# wavefreak.net
KiCad netlist of a schematic drawn in EAGLE
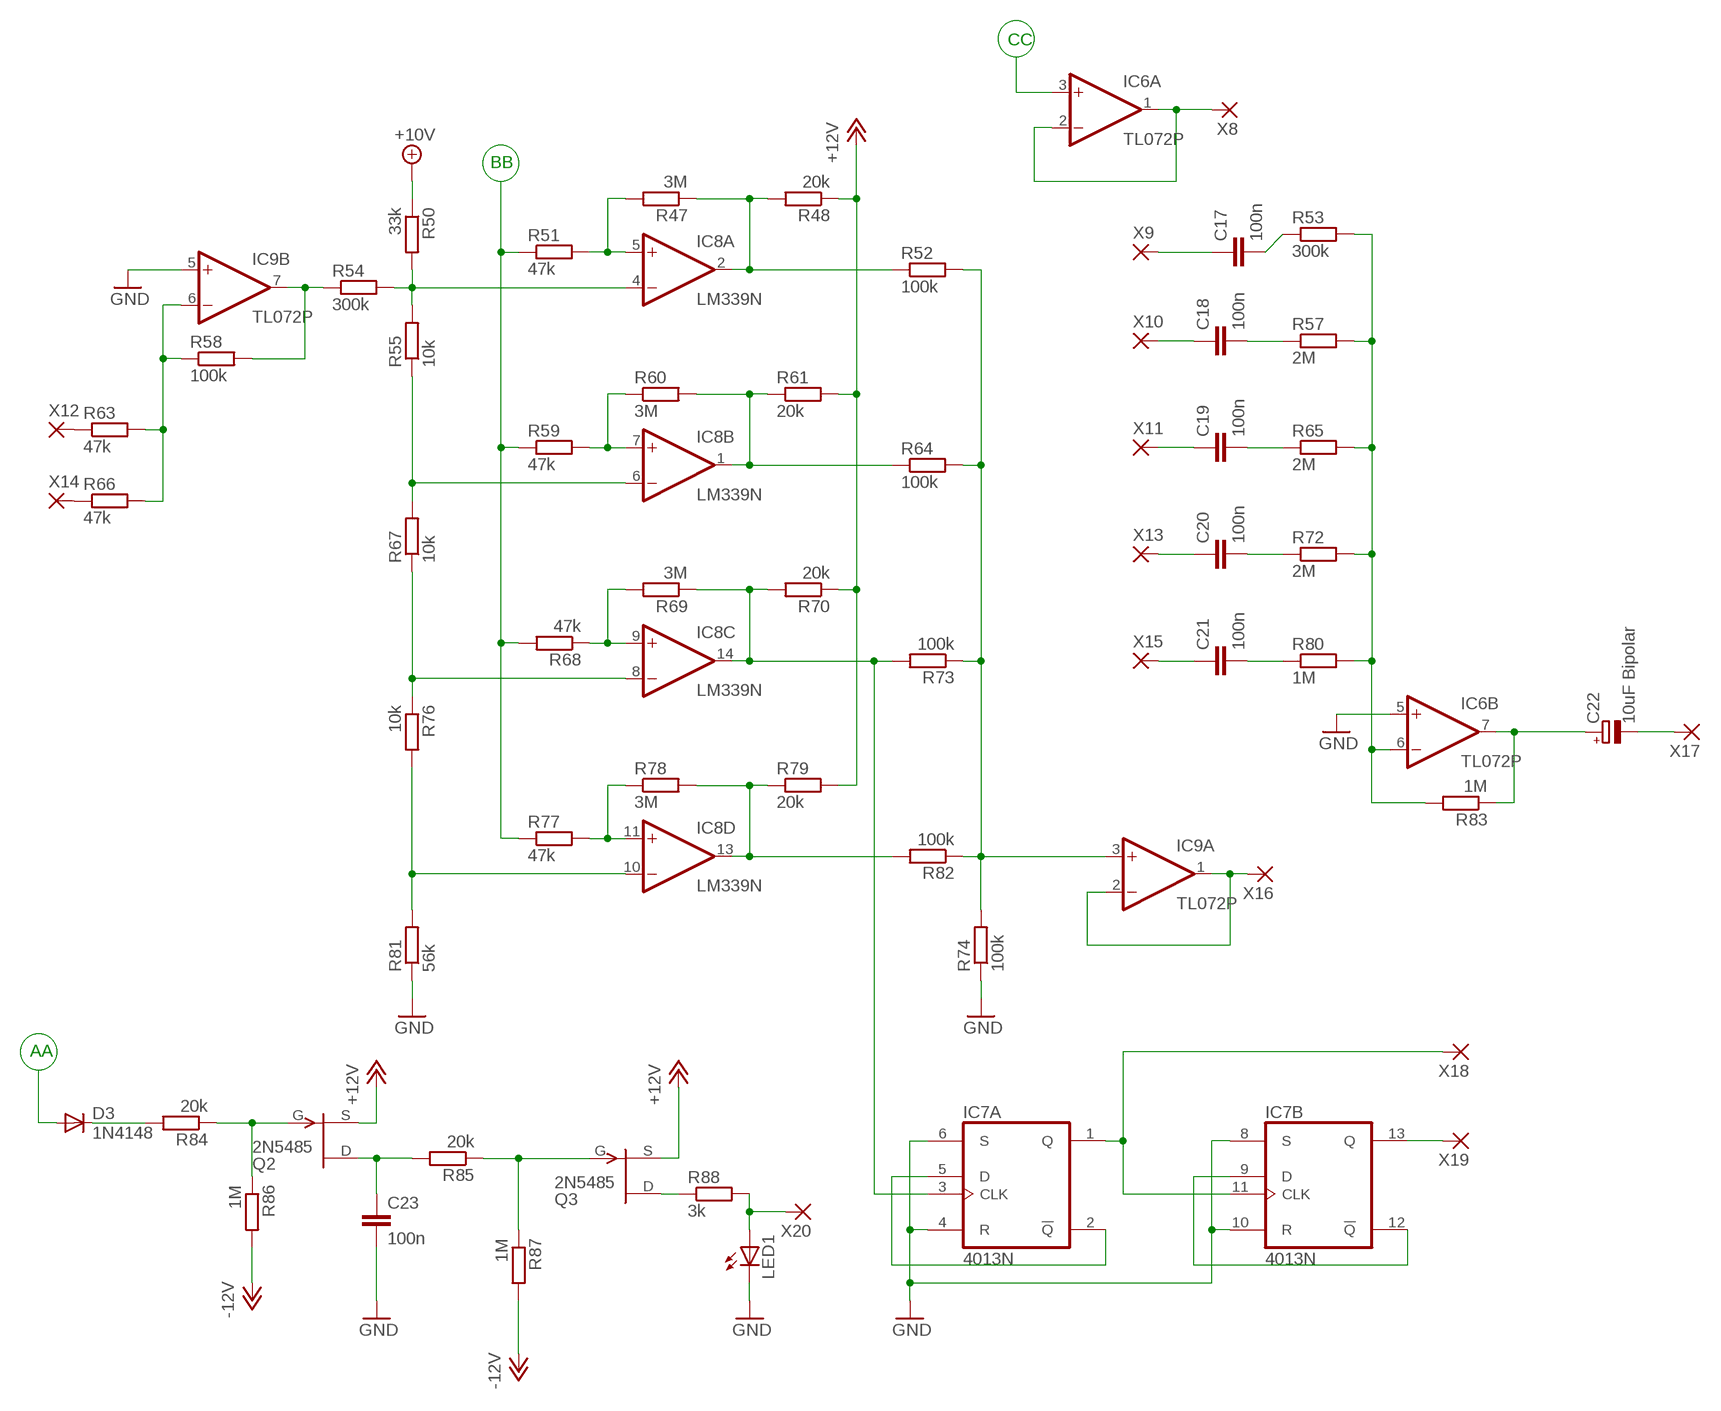
[diagram p0: schematic, sheet 1]
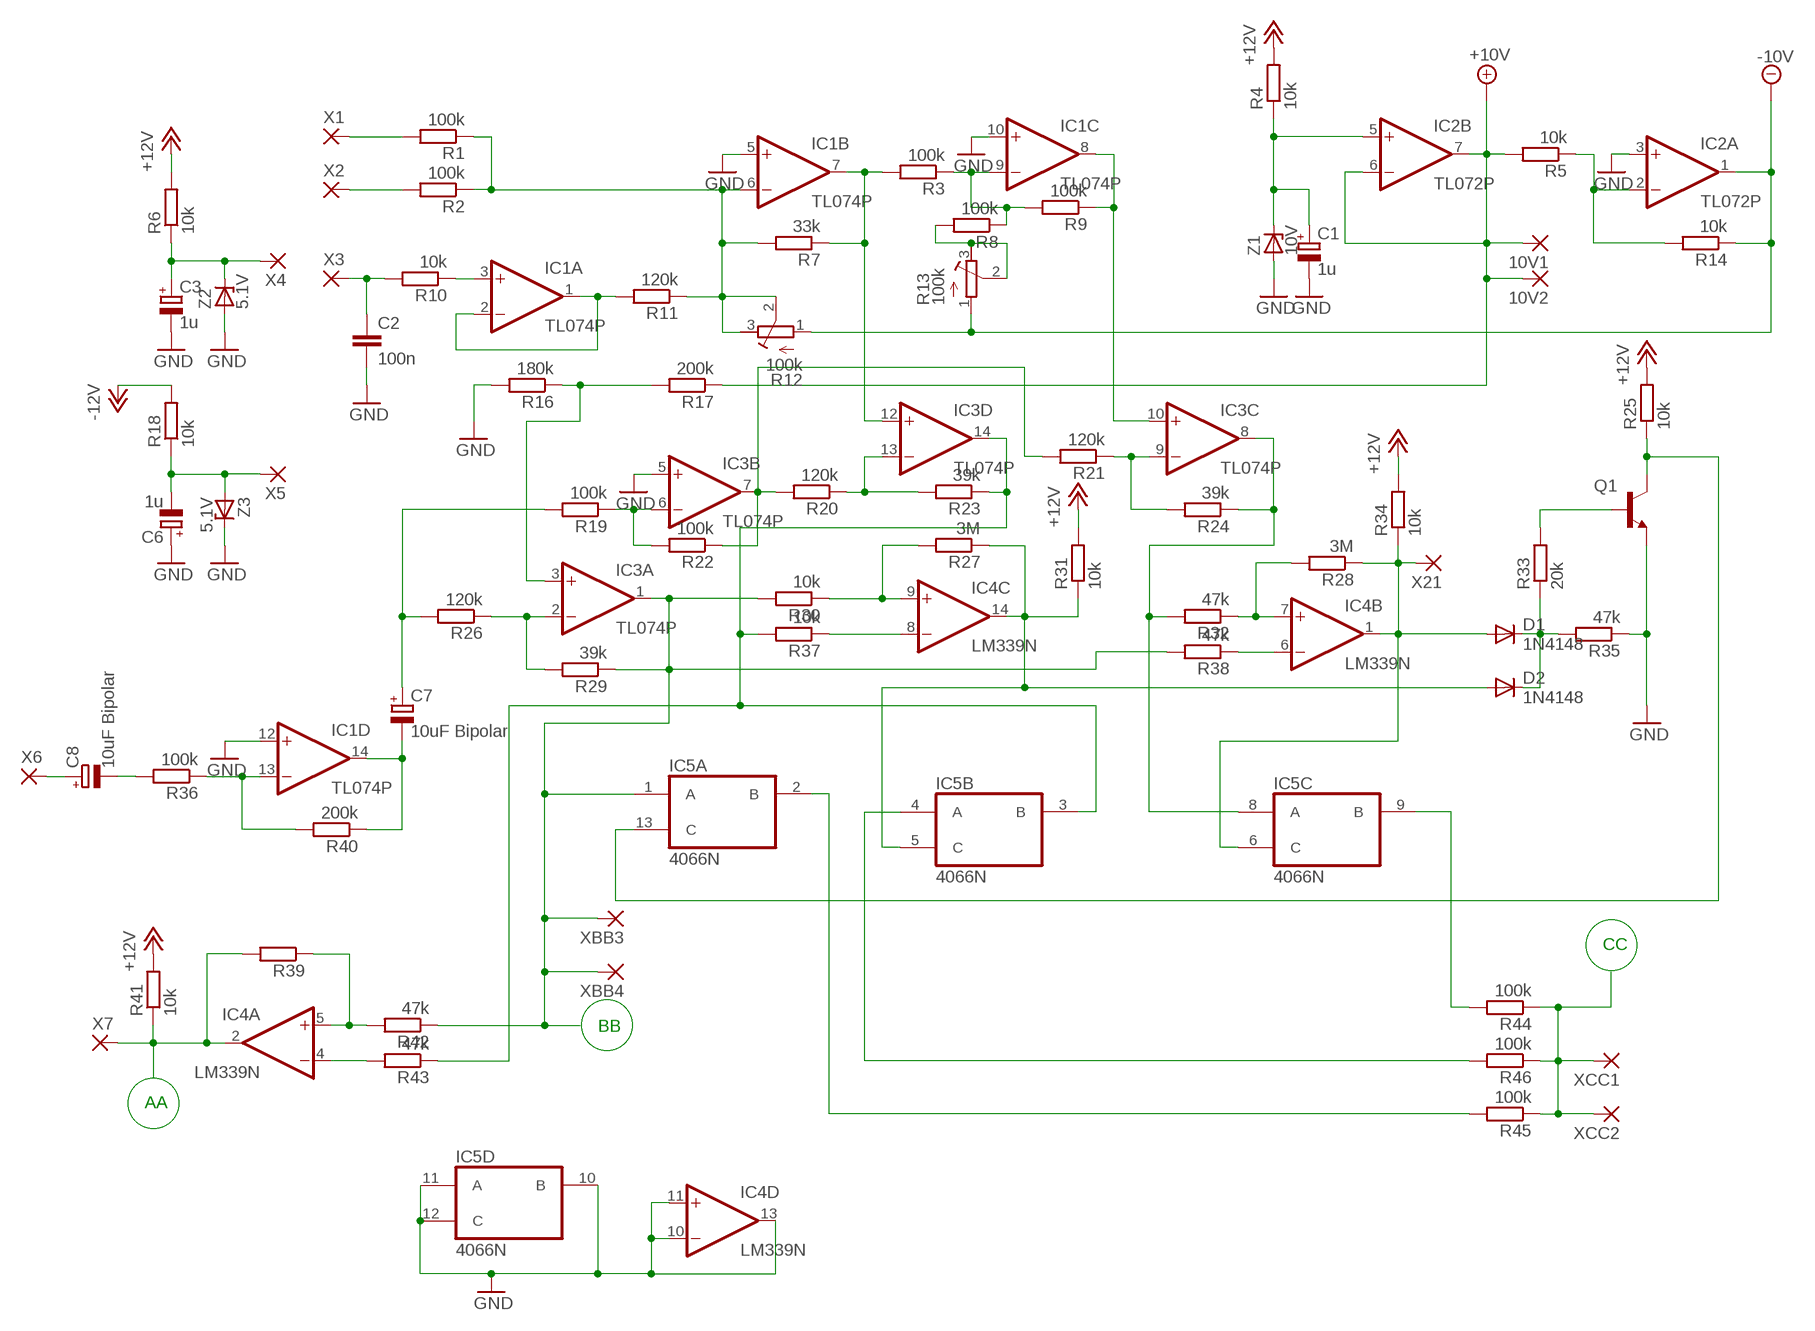
[diagram p1: schematic, sheet 2]
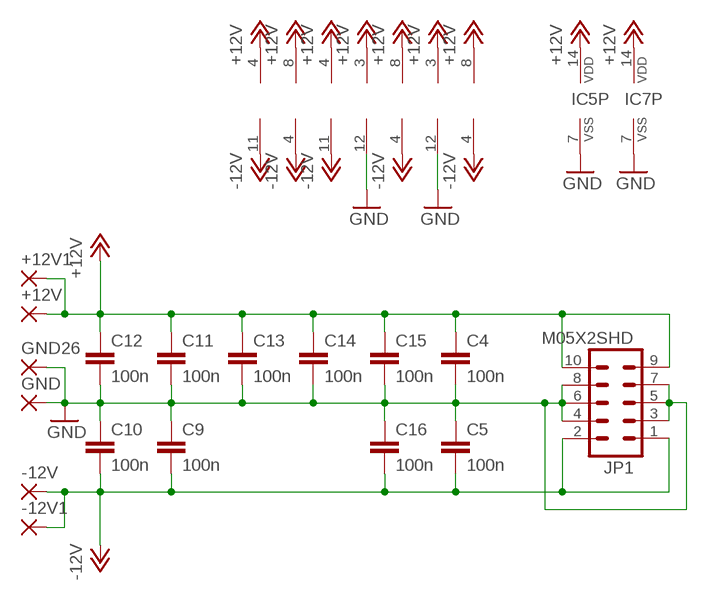
[diagram p2: schematic, sheet 3]

(export (version "E")
  (design (tool "Eeschema 10.0.6"))
  (components
    (comp (ref "+12V")
      (value "2,54/1,0")
      (footprint "eagle-import:2,54_1,0")
      (libsource (lib "eagle-import") (part "2,54/1,0"))
    )
    (comp (ref "+12V1")
      (value "2,54/1,0")
      (footprint "eagle-import:2,54_1,0")
      (libsource (lib "eagle-import") (part "2,54/1,0"))
    )
    (comp (ref "-12V")
      (value "2,54/1,0")
      (footprint "eagle-import:2,54_1,0")
      (libsource (lib "eagle-import") (part "2,54/1,0"))
    )
    (comp (ref "-12V1")
      (value "2,54/1,0")
      (footprint "eagle-import:2,54_1,0")
      (libsource (lib "eagle-import") (part "2,54/1,0"))
    )
    (comp (ref "C4")
      (value "100n")
      (footprint "eagle-import:C025-025X050")
      (libsource (lib "eagle-import") (part "C-EU025-025X050"))
    )
    (comp (ref "C5")
      (value "100n")
      (footprint "eagle-import:C025-025X050")
      (libsource (lib "eagle-import") (part "C-EU025-025X050"))
    )
    (comp (ref "C9")
      (value "100n")
      (footprint "eagle-import:C025-025X050")
      (libsource (lib "eagle-import") (part "C-EU025-025X050"))
    )
    (comp (ref "C10")
      (value "100n")
      (footprint "eagle-import:C025-025X050")
      (libsource (lib "eagle-import") (part "C-EU025-025X050"))
    )
    (comp (ref "C11")
      (value "100n")
      (footprint "eagle-import:C025-025X050")
      (libsource (lib "eagle-import") (part "C-EU025-025X050"))
    )
    (comp (ref "C12")
      (value "100n")
      (footprint "eagle-import:C025-025X050")
      (libsource (lib "eagle-import") (part "C-EU025-025X050"))
    )
    (comp (ref "C13")
      (value "100n")
      (footprint "eagle-import:C025-025X050")
      (libsource (lib "eagle-import") (part "C-EU025-025X050"))
    )
    (comp (ref "C14")
      (value "100n")
      (footprint "eagle-import:C025-025X050")
      (libsource (lib "eagle-import") (part "C-EU025-025X050"))
    )
    (comp (ref "C15")
      (value "100n")
      (footprint "eagle-import:C025-025X050")
      (libsource (lib "eagle-import") (part "C-EU025-025X050"))
    )
    (comp (ref "C16")
      (value "100n")
      (footprint "eagle-import:C025-025X050")
      (libsource (lib "eagle-import") (part "C-EU025-025X050"))
    )
    (comp (ref "GND")
      (value "2,54/1,0")
      (footprint "eagle-import:2,54_1,0")
      (libsource (lib "eagle-import") (part "2,54/1,0"))
    )
    (comp (ref "GND26")
      (value "2,54/1,0")
      (footprint "eagle-import:2,54_1,0")
      (libsource (lib "eagle-import") (part "2,54/1,0"))
    )
    (comp (ref "IC1")
      (value "TL074P")
      (footprint "eagle-import:DIL14")
      (libsource (lib "eagle-import") (part "TL074P"))
    )
    (comp (ref "IC2")
      (value "TL072P")
      (footprint "eagle-import:DIL08")
      (libsource (lib "eagle-import") (part "TL072P"))
    )
    (comp (ref "IC3")
      (value "TL074P")
      (footprint "eagle-import:DIL14")
      (libsource (lib "eagle-import") (part "TL074P"))
    )
    (comp (ref "IC4")
      (value "LM339N")
      (footprint "eagle-import:DIL14")
      (libsource (lib "eagle-import") (part "LM339N"))
    )
    (comp (ref "IC5")
      (value "4066N")
      (footprint "eagle-import:DIL14")
      (libsource (lib "eagle-import") (part "4066N"))
    )
    (comp (ref "IC6")
      (value "TL072P")
      (footprint "eagle-import:DIL08")
      (libsource (lib "eagle-import") (part "TL072P"))
    )
    (comp (ref "IC7")
      (value "4013N")
      (footprint "eagle-import:DIL14")
      (libsource (lib "eagle-import") (part "4013N"))
    )
    (comp (ref "IC8")
      (value "LM339N")
      (footprint "eagle-import:DIL14")
      (libsource (lib "eagle-import") (part "LM339N"))
    )
    (comp (ref "IC9")
      (value "TL072P")
      (footprint "eagle-import:DIL08")
      (libsource (lib "eagle-import") (part "TL072P"))
    )
    (comp (ref "JP1")
      (value "M05X2SHD")
      (footprint "eagle-import:2X5-SHROUDED")
      (libsource (lib "eagle-import") (part "M05X2SHD"))
    )
    (comp (ref "10V1")
      (value "2,54/1,0")
      (footprint "eagle-import:2,54_1,0")
      (libsource (lib "eagle-import") (part "2,54/1,0"))
    )
    (comp (ref "10V2")
      (value "2,54/1,0")
      (footprint "eagle-import:2,54_1,0")
      (libsource (lib "eagle-import") (part "2,54/1,0"))
    )
    (comp (ref "C1")
      (value "1u")
      (footprint "eagle-import:E2,5-5")
      (libsource (lib "eagle-import") (part "CPOL-EUE2.5-5"))
    )
    (comp (ref "C2")
      (value "100n")
      (footprint "eagle-import:C050-025X075")
      (libsource (lib "eagle-import") (part "C-EU050-025X075"))
    )
    (comp (ref "C3")
      (value "1u")
      (footprint "eagle-import:E2,5-5")
      (libsource (lib "eagle-import") (part "CPOL-EUE2.5-5"))
    )
    (comp (ref "C6")
      (value "1u")
      (footprint "eagle-import:E2,5-5")
      (libsource (lib "eagle-import") (part "CPOL-EUE2.5-5"))
    )
    (comp (ref "C7")
      (value "10uF Bipolar")
      (footprint "eagle-import:E3,5-8")
      (libsource (lib "eagle-import") (part "CPOL-EUE3.5-8"))
    )
    (comp (ref "C8")
      (value "10uF Bipolar")
      (footprint "eagle-import:E3,5-8")
      (libsource (lib "eagle-import") (part "CPOL-EUE3.5-8"))
    )
    (comp (ref "D1")
      (value "1N4148")
      (footprint "eagle-import:DO35-7")
      (libsource (lib "eagle-import") (part "1N4148DO35-7"))
    )
    (comp (ref "D2")
      (value "1N4148")
      (footprint "eagle-import:DO35-7")
      (libsource (lib "eagle-import") (part "1N4148DO35-7"))
    )
    (comp (ref "Q1")
      (value "2N3904-NPN-TO92-EBC")
      (footprint "eagle-import:TO92-EBC")
      (libsource (lib "eagle-import") (part "-NPN-TO92-EBC2N3904"))
    )
    (comp (ref "R1")
      (value "100k")
      (footprint "eagle-import:0309V")
      (libsource (lib "eagle-import") (part "R-EU_0309/V"))
    )
    (comp (ref "R2")
      (value "100k")
      (footprint "eagle-import:0309V")
      (libsource (lib "eagle-import") (part "R-EU_0309/V"))
    )
    (comp (ref "R3")
      (value "100k")
      (footprint "eagle-import:0309V")
      (libsource (lib "eagle-import") (part "R-EU_0309/V"))
    )
    (comp (ref "R4")
      (value "10k")
      (footprint "eagle-import:0309V")
      (libsource (lib "eagle-import") (part "R-EU_0309/V"))
    )
    (comp (ref "R5")
      (value "10k")
      (footprint "eagle-import:0309V")
      (libsource (lib "eagle-import") (part "R-EU_0309/V"))
    )
    (comp (ref "R6")
      (value "10k")
      (footprint "eagle-import:0309V")
      (libsource (lib "eagle-import") (part "R-EU_0309/V"))
    )
    (comp (ref "R7")
      (value "33k")
      (footprint "eagle-import:0309V")
      (libsource (lib "eagle-import") (part "R-EU_0309/V"))
    )
    (comp (ref "R8")
      (value "100k")
      (footprint "eagle-import:0309V")
      (libsource (lib "eagle-import") (part "R-EU_0309/V"))
    )
    (comp (ref "R9")
      (value "100k")
      (footprint "eagle-import:0309V")
      (libsource (lib "eagle-import") (part "R-EU_0309/V"))
    )
    (comp (ref "R10")
      (value "10k")
      (footprint "eagle-import:0309V")
      (libsource (lib "eagle-import") (part "R-EU_0309/V"))
    )
    (comp (ref "R11")
      (value "120k")
      (footprint "eagle-import:0309V")
      (libsource (lib "eagle-import") (part "R-EU_0309/V"))
    )
    (comp (ref "R12")
      (value "100k")
      (footprint "eagle-import:RTRIM64W")
      (libsource (lib "eagle-import") (part "R-TRIMM64W"))
    )
    (comp (ref "R13")
      (value "100k")
      (footprint "eagle-import:RTRIM64W")
      (libsource (lib "eagle-import") (part "R-TRIMM64W"))
    )
    (comp (ref "R14")
      (value "10k")
      (footprint "eagle-import:0309V")
      (libsource (lib "eagle-import") (part "R-EU_0309/V"))
    )
    (comp (ref "R16")
      (value "180k")
      (footprint "eagle-import:0309V")
      (libsource (lib "eagle-import") (part "R-EU_0309/V"))
    )
    (comp (ref "R17")
      (value "200k")
      (footprint "eagle-import:0309V")
      (libsource (lib "eagle-import") (part "R-EU_0309/V"))
    )
    (comp (ref "R18")
      (value "10k")
      (footprint "eagle-import:0309V")
      (libsource (lib "eagle-import") (part "R-EU_0309/V"))
    )
    (comp (ref "R19")
      (value "100k")
      (footprint "eagle-import:0309V")
      (libsource (lib "eagle-import") (part "R-EU_0309/V"))
    )
    (comp (ref "R20")
      (value "120k")
      (footprint "eagle-import:0309V")
      (libsource (lib "eagle-import") (part "R-EU_0309/V"))
    )
    (comp (ref "R21")
      (value "120k")
      (footprint "eagle-import:0309V")
      (libsource (lib "eagle-import") (part "R-EU_0309/V"))
    )
    (comp (ref "R22")
      (value "100k")
      (footprint "eagle-import:0309V")
      (libsource (lib "eagle-import") (part "R-EU_0309/V"))
    )
    (comp (ref "R23")
      (value "39k")
      (footprint "eagle-import:0309V")
      (libsource (lib "eagle-import") (part "R-EU_0309/V"))
    )
    (comp (ref "R24")
      (value "39k")
      (footprint "eagle-import:0309V")
      (libsource (lib "eagle-import") (part "R-EU_0309/V"))
    )
    (comp (ref "R25")
      (value "10k")
      (footprint "eagle-import:0309V")
      (libsource (lib "eagle-import") (part "R-EU_0309/V"))
    )
    (comp (ref "R26")
      (value "120k")
      (footprint "eagle-import:0309V")
      (libsource (lib "eagle-import") (part "R-EU_0309/V"))
    )
    (comp (ref "R27")
      (value "3M")
      (footprint "eagle-import:0309V")
      (libsource (lib "eagle-import") (part "R-EU_0309/V"))
    )
    (comp (ref "R28")
      (value "3M")
      (footprint "eagle-import:0309V")
      (libsource (lib "eagle-import") (part "R-EU_0309/V"))
    )
    (comp (ref "R29")
      (value "39k")
      (footprint "eagle-import:0309V")
      (libsource (lib "eagle-import") (part "R-EU_0309/V"))
    )
    (comp (ref "R30")
      (value "10k")
      (footprint "eagle-import:0309V")
      (libsource (lib "eagle-import") (part "R-EU_0309/V"))
    )
    (comp (ref "R31")
      (value "10k")
      (footprint "eagle-import:0309V")
      (libsource (lib "eagle-import") (part "R-EU_0309/V"))
    )
    (comp (ref "R32")
      (value "47k")
      (footprint "eagle-import:0309V")
      (libsource (lib "eagle-import") (part "R-EU_0309/V"))
    )
    (comp (ref "R33")
      (value "20k")
      (footprint "eagle-import:0309V")
      (libsource (lib "eagle-import") (part "R-EU_0309/V"))
    )
    (comp (ref "R34")
      (value "10k")
      (footprint "eagle-import:0309V")
      (libsource (lib "eagle-import") (part "R-EU_0309/V"))
    )
    (comp (ref "R35")
      (value "47k")
      (footprint "eagle-import:0309V")
      (libsource (lib "eagle-import") (part "R-EU_0309/V"))
    )
    (comp (ref "R36")
      (value "100k")
      (footprint "eagle-import:0309V")
      (libsource (lib "eagle-import") (part "R-EU_0309/V"))
    )
    (comp (ref "R37")
      (value "10k")
      (footprint "eagle-import:0309V")
      (libsource (lib "eagle-import") (part "R-EU_0309/V"))
    )
    (comp (ref "R38")
      (value "47k")
      (footprint "eagle-import:0309V")
      (libsource (lib "eagle-import") (part "R-EU_0309/V"))
    )
    (comp (ref "R39")
      (value "R-EU_0309/V")
      (footprint "eagle-import:0309V")
      (libsource (lib "eagle-import") (part "R-EU_0309/V"))
    )
    (comp (ref "R40")
      (value "200k")
      (footprint "eagle-import:0309V")
      (libsource (lib "eagle-import") (part "R-EU_0309/V"))
    )
    (comp (ref "R41")
      (value "10k")
      (footprint "eagle-import:0309V")
      (libsource (lib "eagle-import") (part "R-EU_0309/V"))
    )
    (comp (ref "R42")
      (value "47k")
      (footprint "eagle-import:0309V")
      (libsource (lib "eagle-import") (part "R-EU_0309/V"))
    )
    (comp (ref "R43")
      (value "47k")
      (footprint "eagle-import:0309V")
      (libsource (lib "eagle-import") (part "R-EU_0309/V"))
    )
    (comp (ref "R44")
      (value "100k")
      (footprint "eagle-import:0309V")
      (libsource (lib "eagle-import") (part "R-EU_0309/V"))
    )
    (comp (ref "R45")
      (value "100k")
      (footprint "eagle-import:0309V")
      (libsource (lib "eagle-import") (part "R-EU_0309/V"))
    )
    (comp (ref "R46")
      (value "100k")
      (footprint "eagle-import:0309V")
      (libsource (lib "eagle-import") (part "R-EU_0309/V"))
    )
    (comp (ref "X1")
      (value "2,54/1,0")
      (footprint "eagle-import:2,54_1,0")
      (libsource (lib "eagle-import") (part "2,54/1,0"))
    )
    (comp (ref "X2")
      (value "2,54/1,0")
      (footprint "eagle-import:2,54_1,0")
      (libsource (lib "eagle-import") (part "2,54/1,0"))
    )
    (comp (ref "X3")
      (value "2,54/1,0")
      (footprint "eagle-import:2,54_1,0")
      (libsource (lib "eagle-import") (part "2,54/1,0"))
    )
    (comp (ref "X4")
      (value "2,54/1,0")
      (footprint "eagle-import:2,54_1,0")
      (libsource (lib "eagle-import") (part "2,54/1,0"))
    )
    (comp (ref "X5")
      (value "2,54/1,0")
      (footprint "eagle-import:2,54_1,0")
      (libsource (lib "eagle-import") (part "2,54/1,0"))
    )
    (comp (ref "X6")
      (value "2,54/1,0")
      (footprint "eagle-import:2,54_1,0")
      (libsource (lib "eagle-import") (part "2,54/1,0"))
    )
    (comp (ref "X7")
      (value "2,54/1,0")
      (footprint "eagle-import:2,54_1,0")
      (libsource (lib "eagle-import") (part "2,54/1,0"))
    )
    (comp (ref "X21")
      (value "2,54/1,0")
      (footprint "eagle-import:2,54_1,0")
      (libsource (lib "eagle-import") (part "2,54/1,0"))
    )
    (comp (ref "XBB3")
      (value "2,54/1,0")
      (footprint "eagle-import:2,54_1,0")
      (libsource (lib "eagle-import") (part "2,54/1,0"))
    )
    (comp (ref "XBB4")
      (value "2,54/1,0")
      (footprint "eagle-import:2,54_1,0")
      (libsource (lib "eagle-import") (part "2,54/1,0"))
    )
    (comp (ref "XCC1")
      (value "2,54/1,0")
      (footprint "eagle-import:2,54_1,0")
      (libsource (lib "eagle-import") (part "2,54/1,0"))
    )
    (comp (ref "XCC2")
      (value "2,54/1,0")
      (footprint "eagle-import:2,54_1,0")
      (libsource (lib "eagle-import") (part "2,54/1,0"))
    )
    (comp (ref "Z1")
      (value "10V")
      (footprint "eagle-import:DO34Z7")
      (libsource (lib "eagle-import") (part "BZV10"))
    )
    (comp (ref "Z2")
      (value "5.1V")
      (footprint "eagle-import:DO34Z7")
      (libsource (lib "eagle-import") (part "BZV10"))
    )
    (comp (ref "Z3")
      (value "5.1V")
      (footprint "eagle-import:DO34Z7")
      (libsource (lib "eagle-import") (part "BZV10"))
    )
    (comp (ref "C17")
      (value "100n")
      (footprint "eagle-import:C050-025X075")
      (libsource (lib "eagle-import") (part "C-EU050-025X075"))
    )
    (comp (ref "C18")
      (value "100n")
      (footprint "eagle-import:C050-025X075")
      (libsource (lib "eagle-import") (part "C-EU050-025X075"))
    )
    (comp (ref "C19")
      (value "100n")
      (footprint "eagle-import:C050-025X075")
      (libsource (lib "eagle-import") (part "C-EU050-025X075"))
    )
    (comp (ref "C20")
      (value "100n")
      (footprint "eagle-import:C050-025X075")
      (libsource (lib "eagle-import") (part "C-EU050-025X075"))
    )
    (comp (ref "C21")
      (value "100n")
      (footprint "eagle-import:C050-025X075")
      (libsource (lib "eagle-import") (part "C-EU050-025X075"))
    )
    (comp (ref "C22")
      (value "10uF Bipolar")
      (footprint "eagle-import:E3,5-8")
      (libsource (lib "eagle-import") (part "CPOL-EUE3.5-8"))
    )
    (comp (ref "C23")
      (value "100n")
      (footprint "eagle-import:C050-025X075")
      (libsource (lib "eagle-import") (part "C-EU050-025X075"))
    )
    (comp (ref "D3")
      (value "1N4148")
      (footprint "eagle-import:DO35-7")
      (libsource (lib "eagle-import") (part "1N4148DO35-7"))
    )
    (comp (ref "LED1")
      (value "LED3MM")
      (footprint "eagle-import:LED3MM")
      (libsource (lib "eagle-import") (part "LED3MM"))
    )
    (comp (ref "Q2")
      (value "2N5485")
      (footprint "eagle-import:TO92-")
      (libsource (lib "eagle-import") (part "?5482N5"))
    )
    (comp (ref "Q3")
      (value "2N5485")
      (footprint "eagle-import:TO92-")
      (libsource (lib "eagle-import") (part "?5482N5"))
    )
    (comp (ref "R47")
      (value "3M")
      (footprint "eagle-import:0309_10")
      (libsource (lib "eagle-import") (part "R-EU_0309/10"))
    )
    (comp (ref "R48")
      (value "20k")
      (footprint "eagle-import:0309_10")
      (libsource (lib "eagle-import") (part "R-EU_0309/10"))
    )
    (comp (ref "R50")
      (value "33k")
      (footprint "eagle-import:0309_10")
      (libsource (lib "eagle-import") (part "R-EU_0309/10"))
    )
    (comp (ref "R51")
      (value "47k")
      (footprint "eagle-import:0309_10")
      (libsource (lib "eagle-import") (part "R-EU_0309/10"))
    )
    (comp (ref "R52")
      (value "100k")
      (footprint "eagle-import:0309_10")
      (libsource (lib "eagle-import") (part "R-EU_0309/10"))
    )
    (comp (ref "R53")
      (value "300k")
      (footprint "eagle-import:0309V")
      (libsource (lib "eagle-import") (part "R-EU_0309/V"))
    )
    (comp (ref "R54")
      (value "300k")
      (footprint "eagle-import:0309V")
      (libsource (lib "eagle-import") (part "R-EU_0309/V"))
    )
    (comp (ref "R55")
      (value "10k")
      (footprint "eagle-import:0309_10")
      (libsource (lib "eagle-import") (part "R-EU_0309/10"))
    )
    (comp (ref "R57")
      (value "2M")
      (footprint "eagle-import:0309V")
      (libsource (lib "eagle-import") (part "R-EU_0309/V"))
    )
    (comp (ref "R58")
      (value "100k")
      (footprint "eagle-import:0309V")
      (libsource (lib "eagle-import") (part "R-EU_0309/V"))
    )
    (comp (ref "R59")
      (value "47k")
      (footprint "eagle-import:0309_10")
      (libsource (lib "eagle-import") (part "R-EU_0309/10"))
    )
    (comp (ref "R60")
      (value "3M")
      (footprint "eagle-import:0309_10")
      (libsource (lib "eagle-import") (part "R-EU_0309/10"))
    )
    (comp (ref "R61")
      (value "20k")
      (footprint "eagle-import:0309_10")
      (libsource (lib "eagle-import") (part "R-EU_0309/10"))
    )
    (comp (ref "R63")
      (value "47k")
      (footprint "eagle-import:0309V")
      (libsource (lib "eagle-import") (part "R-EU_0309/V"))
    )
    (comp (ref "R64")
      (value "100k")
      (footprint "eagle-import:0309_10")
      (libsource (lib "eagle-import") (part "R-EU_0309/10"))
    )
    (comp (ref "R65")
      (value "2M")
      (footprint "eagle-import:0309V")
      (libsource (lib "eagle-import") (part "R-EU_0309/V"))
    )
    (comp (ref "R66")
      (value "47k")
      (footprint "eagle-import:0309V")
      (libsource (lib "eagle-import") (part "R-EU_0309/V"))
    )
    (comp (ref "R67")
      (value "10k")
      (footprint "eagle-import:0309_10")
      (libsource (lib "eagle-import") (part "R-EU_0309/10"))
    )
    (comp (ref "R68")
      (value "47k")
      (footprint "eagle-import:0309_10")
      (libsource (lib "eagle-import") (part "R-EU_0309/10"))
    )
    (comp (ref "R69")
      (value "3M")
      (footprint "eagle-import:0309_10")
      (libsource (lib "eagle-import") (part "R-EU_0309/10"))
    )
    (comp (ref "R70")
      (value "20k")
      (footprint "eagle-import:0309_10")
      (libsource (lib "eagle-import") (part "R-EU_0309/10"))
    )
    (comp (ref "R72")
      (value "2M")
      (footprint "eagle-import:0309V")
      (libsource (lib "eagle-import") (part "R-EU_0309/V"))
    )
    (comp (ref "R73")
      (value "100k")
      (footprint "eagle-import:0309_10")
      (libsource (lib "eagle-import") (part "R-EU_0309/10"))
    )
    (comp (ref "R74")
      (value "100k")
      (footprint "eagle-import:0309_10")
      (libsource (lib "eagle-import") (part "R-EU_0309/10"))
    )
    (comp (ref "R76")
      (value "10k")
      (footprint "eagle-import:0309_10")
      (libsource (lib "eagle-import") (part "R-EU_0309/10"))
    )
    (comp (ref "R77")
      (value "47k")
      (footprint "eagle-import:0309_10")
      (libsource (lib "eagle-import") (part "R-EU_0309/10"))
    )
    (comp (ref "R78")
      (value "3M")
      (footprint "eagle-import:0309_10")
      (libsource (lib "eagle-import") (part "R-EU_0309/10"))
    )
    (comp (ref "R79")
      (value "20k")
      (footprint "eagle-import:0309_10")
      (libsource (lib "eagle-import") (part "R-EU_0309/10"))
    )
    (comp (ref "R80")
      (value "1M")
      (footprint "eagle-import:0309V")
      (libsource (lib "eagle-import") (part "R-EU_0309/V"))
    )
    (comp (ref "R81")
      (value "56k")
      (footprint "eagle-import:0309_10")
      (libsource (lib "eagle-import") (part "R-EU_0309/10"))
    )
    (comp (ref "R82")
      (value "100k")
      (footprint "eagle-import:0309_10")
      (libsource (lib "eagle-import") (part "R-EU_0309/10"))
    )
    (comp (ref "R83")
      (value "1M")
      (footprint "eagle-import:0309V")
      (libsource (lib "eagle-import") (part "R-EU_0309/V"))
    )
    (comp (ref "R84")
      (value "20k")
      (footprint "eagle-import:0309V")
      (libsource (lib "eagle-import") (part "R-EU_0309/V"))
    )
    (comp (ref "R85")
      (value "20k")
      (footprint "eagle-import:0309V")
      (libsource (lib "eagle-import") (part "R-EU_0309/V"))
    )
    (comp (ref "R86")
      (value "1M")
      (footprint "eagle-import:0309V")
      (libsource (lib "eagle-import") (part "R-EU_0309/V"))
    )
    (comp (ref "R87")
      (value "1M")
      (footprint "eagle-import:0309V")
      (libsource (lib "eagle-import") (part "R-EU_0309/V"))
    )
    (comp (ref "R88")
      (value "3k")
      (footprint "eagle-import:0309V")
      (libsource (lib "eagle-import") (part "R-EU_0309/V"))
    )
    (comp (ref "X8")
      (value "2,54/1,0")
      (footprint "eagle-import:2,54_1,0")
      (libsource (lib "eagle-import") (part "2,54/1,0"))
    )
    (comp (ref "X9")
      (value "2,54/1,0")
      (footprint "eagle-import:2,54_1,0")
      (libsource (lib "eagle-import") (part "2,54/1,0"))
    )
    (comp (ref "X10")
      (value "2,54/1,0")
      (footprint "eagle-import:2,54_1,0")
      (libsource (lib "eagle-import") (part "2,54/1,0"))
    )
    (comp (ref "X11")
      (value "2,54/1,0")
      (footprint "eagle-import:2,54_1,0")
      (libsource (lib "eagle-import") (part "2,54/1,0"))
    )
    (comp (ref "X12")
      (value "2,54/1,0")
      (footprint "eagle-import:2,54_1,0")
      (libsource (lib "eagle-import") (part "2,54/1,0"))
    )
    (comp (ref "X13")
      (value "2,54/1,0")
      (footprint "eagle-import:2,54_1,0")
      (libsource (lib "eagle-import") (part "2,54/1,0"))
    )
    (comp (ref "X14")
      (value "2,54/1,0")
      (footprint "eagle-import:2,54_1,0")
      (libsource (lib "eagle-import") (part "2,54/1,0"))
    )
    (comp (ref "X15")
      (value "2,54/1,0")
      (footprint "eagle-import:2,54_1,0")
      (libsource (lib "eagle-import") (part "2,54/1,0"))
    )
    (comp (ref "X16")
      (value "2,54/1,0")
      (footprint "eagle-import:2,54_1,0")
      (libsource (lib "eagle-import") (part "2,54/1,0"))
    )
    (comp (ref "X17")
      (value "2,54/1,0")
      (footprint "eagle-import:2,54_1,0")
      (libsource (lib "eagle-import") (part "2,54/1,0"))
    )
    (comp (ref "X18")
      (value "2,54/1,0")
      (footprint "eagle-import:2,54_1,0")
      (libsource (lib "eagle-import") (part "2,54/1,0"))
    )
    (comp (ref "X19")
      (value "2,54/1,0")
      (footprint "eagle-import:2,54_1,0")
      (libsource (lib "eagle-import") (part "2,54/1,0"))
    )
    (comp (ref "X20")
      (value "2,54/1,0")
      (footprint "eagle-import:2,54_1,0")
      (libsource (lib "eagle-import") (part "2,54/1,0"))
    )
  )
  (nets
    (net (code "1") (name "+10V") (class "Default")
      (node (ref "10V1") (pin "1") (pinfunction "P_1") (pintype "passive"))
      (node (ref "10V2") (pin "1") (pinfunction "P_1") (pintype "passive"))
      (node (ref "IC2") (pin "6") (pinfunction "-IN_6") (pintype "input"))
      (node (ref "IC2") (pin "7") (pinfunction "OUT_7") (pintype "output"))
      (node (ref "R17") (pin "1") (pinfunction "1_1") (pintype "passive"))
      (node (ref "R5") (pin "2") (pinfunction "2_2") (pintype "passive"))
      (node (ref "R50") (pin "1") (pinfunction "1_1") (pintype "passive"))
    )
    (net (code "2") (name "+12V") (class "Default")
      (node (ref "+12V") (pin "1") (pinfunction "P_1") (pintype "passive"))
      (node (ref "+12V1") (pin "1") (pinfunction "P_1") (pintype "passive"))
      (node (ref "C11") (pin "1") (pinfunction "1_1") (pintype "passive"))
      (node (ref "C12") (pin "1") (pinfunction "1_1") (pintype "passive"))
      (node (ref "C13") (pin "1") (pinfunction "1_1") (pintype "passive"))
      (node (ref "C14") (pin "1") (pinfunction "1_1") (pintype "passive"))
      (node (ref "C15") (pin "1") (pinfunction "1_1") (pintype "passive"))
      (node (ref "C4") (pin "1") (pinfunction "1_1") (pintype "passive"))
      (node (ref "IC1") (pin "4") (pinfunction "V+_4") (pintype "power_in"))
      (node (ref "IC2") (pin "8") (pinfunction "V+_8") (pintype "power_in"))
      (node (ref "IC3") (pin "4") (pinfunction "V+_4") (pintype "power_in"))
      (node (ref "IC4") (pin "3") (pinfunction "V+_3") (pintype "power_in"))
      (node (ref "IC5") (pin "14") (pinfunction "VDD_14") (pintype "power_in"))
      (node (ref "IC6") (pin "8") (pinfunction "V+_8") (pintype "power_in"))
      (node (ref "IC7") (pin "14") (pinfunction "VDD_14") (pintype "power_in"))
      (node (ref "IC8") (pin "3") (pinfunction "V+_3") (pintype "power_in"))
      (node (ref "IC9") (pin "8") (pinfunction "V+_8") (pintype "power_in"))
      (node (ref "JP1") (pin "10") (pinfunction "10_10") (pintype "passive"))
      (node (ref "JP1") (pin "9") (pinfunction "9_9") (pintype "passive"))
      (node (ref "Q2") (pin "2") (pinfunction "S_2") (pintype "passive"))
      (node (ref "Q3") (pin "2") (pinfunction "S_2") (pintype "passive"))
      (node (ref "R25") (pin "2") (pinfunction "2_2") (pintype "passive"))
      (node (ref "R31") (pin "2") (pinfunction "2_2") (pintype "passive"))
      (node (ref "R34") (pin "2") (pinfunction "2_2") (pintype "passive"))
      (node (ref "R4") (pin "2") (pinfunction "2_2") (pintype "passive"))
      (node (ref "R41") (pin "2") (pinfunction "2_2") (pintype "passive"))
      (node (ref "R48") (pin "1") (pinfunction "1_1") (pintype "passive"))
      (node (ref "R6") (pin "2") (pinfunction "2_2") (pintype "passive"))
      (node (ref "R61") (pin "2") (pinfunction "2_2") (pintype "passive"))
      (node (ref "R70") (pin "1") (pinfunction "1_1") (pintype "passive"))
      (node (ref "R79") (pin "2") (pinfunction "2_2") (pintype "passive"))
    )
    (net (code "3") (name "-10V") (class "Default")
      (node (ref "IC2") (pin "1") (pinfunction "OUT_1") (pintype "output"))
      (node (ref "R12") (pin "1") (pinfunction "A_1") (pintype "passive"))
      (node (ref "R13") (pin "1") (pinfunction "A_1") (pintype "passive"))
      (node (ref "R14") (pin "1") (pinfunction "1_1") (pintype "passive"))
    )
    (net (code "4") (name "-12V") (class "Default")
      (node (ref "-12V") (pin "1") (pinfunction "P_1") (pintype "passive"))
      (node (ref "-12V1") (pin "1") (pinfunction "P_1") (pintype "passive"))
      (node (ref "C10") (pin "2") (pinfunction "2_2") (pintype "passive"))
      (node (ref "C16") (pin "2") (pinfunction "2_2") (pintype "passive"))
      (node (ref "C5") (pin "2") (pinfunction "2_2") (pintype "passive"))
      (node (ref "C9") (pin "2") (pinfunction "2_2") (pintype "passive"))
      (node (ref "IC1") (pin "11") (pinfunction "V-_11") (pintype "power_in"))
      (node (ref "IC2") (pin "4") (pinfunction "V-_4") (pintype "power_in"))
      (node (ref "IC3") (pin "11") (pinfunction "V-_11") (pintype "power_in"))
      (node (ref "IC6") (pin "4") (pinfunction "V-_4") (pintype "power_in"))
      (node (ref "IC9") (pin "4") (pinfunction "V-_4") (pintype "power_in"))
      (node (ref "JP1") (pin "1") (pinfunction "1_1") (pintype "passive"))
      (node (ref "JP1") (pin "2") (pinfunction "2_2") (pintype "passive"))
      (node (ref "R18") (pin "2") (pinfunction "2_2") (pintype "passive"))
      (node (ref "R86") (pin "2") (pinfunction "2_2") (pintype "passive"))
      (node (ref "R87") (pin "2") (pinfunction "2_2") (pintype "passive"))
    )
    (net (code "5") (name "AA") (class "Default")
      (node (ref "D3") (pin "A") (pinfunction "A_A") (pintype "passive"))
      (node (ref "IC4") (pin "2") (pinfunction "OUT_2") (pintype "open_collector"))
      (node (ref "R39") (pin "2") (pinfunction "2_2") (pintype "passive"))
      (node (ref "R41") (pin "1") (pinfunction "1_1") (pintype "passive"))
      (node (ref "X7") (pin "1") (pinfunction "P_1") (pintype "passive"))
    )
    (net (code "6") (name "BB") (class "Default")
      (node (ref "IC3") (pin "1") (pinfunction "OUT_1") (pintype "output"))
      (node (ref "IC5") (pin "1") (pinfunction "A_1") (pintype "tri_state"))
      (node (ref "R29") (pin "1") (pinfunction "1_1") (pintype "passive"))
      (node (ref "R30") (pin "2") (pinfunction "2_2") (pintype "passive"))
      (node (ref "R38") (pin "2") (pinfunction "2_2") (pintype "passive"))
      (node (ref "R42") (pin "1") (pinfunction "1_1") (pintype "passive"))
      (node (ref "R51") (pin "1") (pinfunction "1_1") (pintype "passive"))
      (node (ref "R59") (pin "1") (pinfunction "1_1") (pintype "passive"))
      (node (ref "R68") (pin "2") (pinfunction "2_2") (pintype "passive"))
      (node (ref "R77") (pin "1") (pinfunction "1_1") (pintype "passive"))
      (node (ref "XBB3") (pin "1") (pinfunction "P_1") (pintype "passive"))
      (node (ref "XBB4") (pin "1") (pinfunction "P_1") (pintype "passive"))
    )
    (net (code "7") (name "CC") (class "Default")
      (node (ref "IC6") (pin "3") (pinfunction "+IN_3") (pintype "input"))
      (node (ref "R44") (pin "1") (pinfunction "1_1") (pintype "passive"))
      (node (ref "R45") (pin "1") (pinfunction "1_1") (pintype "passive"))
      (node (ref "R46") (pin "1") (pinfunction "1_1") (pintype "passive"))
      (node (ref "XCC1") (pin "1") (pinfunction "P_1") (pintype "passive"))
      (node (ref "XCC2") (pin "1") (pinfunction "P_1") (pintype "passive"))
    )
    (net (code "8") (name "GND") (class "Default")
      (node (ref "C1") (pin "-") (pinfunction "-_-") (pintype "passive"))
      (node (ref "C10") (pin "1") (pinfunction "1_1") (pintype "passive"))
      (node (ref "C11") (pin "2") (pinfunction "2_2") (pintype "passive"))
      (node (ref "C12") (pin "2") (pinfunction "2_2") (pintype "passive"))
      (node (ref "C13") (pin "2") (pinfunction "2_2") (pintype "passive"))
      (node (ref "C14") (pin "2") (pinfunction "2_2") (pintype "passive"))
      (node (ref "C15") (pin "2") (pinfunction "2_2") (pintype "passive"))
      (node (ref "C16") (pin "1") (pinfunction "1_1") (pintype "passive"))
      (node (ref "C2") (pin "2") (pinfunction "2_2") (pintype "passive"))
      (node (ref "C23") (pin "2") (pinfunction "2_2") (pintype "passive"))
      (node (ref "C3") (pin "-") (pinfunction "-_-") (pintype "passive"))
      (node (ref "C4") (pin "2") (pinfunction "2_2") (pintype "passive"))
      (node (ref "C5") (pin "1") (pinfunction "1_1") (pintype "passive"))
      (node (ref "C6") (pin "+") (pinfunction "+_+") (pintype "passive"))
      (node (ref "C9") (pin "1") (pinfunction "1_1") (pintype "passive"))
      (node (ref "GND") (pin "1") (pinfunction "P_1") (pintype "passive"))
      (node (ref "GND26") (pin "1") (pinfunction "P_1") (pintype "passive"))
      (node (ref "IC1") (pin "10") (pinfunction "+IN_10") (pintype "input"))
      (node (ref "IC1") (pin "12") (pinfunction "+IN_12") (pintype "input"))
      (node (ref "IC1") (pin "5") (pinfunction "+IN_5") (pintype "input"))
      (node (ref "IC2") (pin "3") (pinfunction "+IN_3") (pintype "input"))
      (node (ref "IC3") (pin "5") (pinfunction "+IN_5") (pintype "input"))
      (node (ref "IC4") (pin "10") (pinfunction "-IN_10") (pintype "input"))
      (node (ref "IC4") (pin "11") (pinfunction "+IN_11") (pintype "input"))
      (node (ref "IC4") (pin "12") (pinfunction "GND_12") (pintype "power_in"))
      (node (ref "IC4") (pin "13") (pinfunction "OUT_13") (pintype "open_collector"))
      (node (ref "IC5") (pin "10") (pinfunction "B_10") (pintype "tri_state"))
      (node (ref "IC5") (pin "11") (pinfunction "A_11") (pintype "tri_state"))
      (node (ref "IC5") (pin "12") (pinfunction "C_12") (pintype "input"))
      (node (ref "IC5") (pin "7") (pinfunction "VSS_7") (pintype "power_in"))
      (node (ref "IC6") (pin "5") (pinfunction "+IN_5") (pintype "input"))
      (node (ref "IC7") (pin "10") (pinfunction "R_10") (pintype "input"))
      (node (ref "IC7") (pin "4") (pinfunction "R_4") (pintype "input"))
      (node (ref "IC7") (pin "6") (pinfunction "S_6") (pintype "input"))
      (node (ref "IC7") (pin "7") (pinfunction "VSS_7") (pintype "power_in"))
      (node (ref "IC7") (pin "8") (pinfunction "S_8") (pintype "input"))
      (node (ref "IC8") (pin "12") (pinfunction "GND_12") (pintype "power_in"))
      (node (ref "IC9") (pin "5") (pinfunction "+IN_5") (pintype "input"))
      (node (ref "JP1") (pin "3") (pinfunction "3_3") (pintype "passive"))
      (node (ref "JP1") (pin "4") (pinfunction "4_4") (pintype "passive"))
      (node (ref "JP1") (pin "5") (pinfunction "5_5") (pintype "passive"))
      (node (ref "JP1") (pin "6") (pinfunction "6_6") (pintype "passive"))
      (node (ref "JP1") (pin "7") (pinfunction "7_7") (pintype "passive"))
      (node (ref "JP1") (pin "8") (pinfunction "8_8") (pintype "passive"))
      (node (ref "LED1") (pin "K") (pinfunction "C_K") (pintype "passive"))
      (node (ref "Q1") (pin "E") (pinfunction "E_E") (pintype "passive"))
      (node (ref "R16") (pin "2") (pinfunction "2_2") (pintype "passive"))
      (node (ref "R35") (pin "1") (pinfunction "1_1") (pintype "passive"))
      (node (ref "R74") (pin "1") (pinfunction "1_1") (pintype "passive"))
      (node (ref "R81") (pin "1") (pinfunction "1_1") (pintype "passive"))
      (node (ref "Z1") (pin "A") (pinfunction "A_A") (pintype "passive"))
      (node (ref "Z2") (pin "A") (pinfunction "A_A") (pintype "passive"))
      (node (ref "Z3") (pin "C") (pinfunction "C_C") (pintype "passive"))
    )
    (net (code "9") (name "Net-(C7-Pad+)") (class "Default")
      (node (ref "C7") (pin "+") (pinfunction "+_+") (pintype "passive"))
      (node (ref "R19") (pin "2") (pinfunction "2_2") (pintype "passive"))
      (node (ref "R26") (pin "2") (pinfunction "2_2") (pintype "passive"))
    )
    (net (code "10") (name "Net-(C8-Pad-)") (class "Default")
      (node (ref "C8") (pin "-") (pinfunction "-_-") (pintype "passive"))
      (node (ref "R36") (pin "2") (pinfunction "2_2") (pintype "passive"))
    )
    (net (code "11") (name "Net-(C17-Pad2)") (class "Default")
      (node (ref "C17") (pin "2") (pinfunction "2_2") (pintype "passive"))
      (node (ref "R53") (pin "1") (pinfunction "1_1") (pintype "passive"))
    )
    (net (code "12") (name "Net-(C18-Pad2)") (class "Default")
      (node (ref "C18") (pin "2") (pinfunction "2_2") (pintype "passive"))
      (node (ref "R57") (pin "1") (pinfunction "1_1") (pintype "passive"))
    )
    (net (code "13") (name "Net-(C19-Pad2)") (class "Default")
      (node (ref "C19") (pin "2") (pinfunction "2_2") (pintype "passive"))
      (node (ref "R65") (pin "1") (pinfunction "1_1") (pintype "passive"))
    )
    (net (code "14") (name "Net-(C20-Pad2)") (class "Default")
      (node (ref "C20") (pin "2") (pinfunction "2_2") (pintype "passive"))
      (node (ref "R72") (pin "1") (pinfunction "1_1") (pintype "passive"))
    )
    (net (code "15") (name "Net-(C21-Pad2)") (class "Default")
      (node (ref "C21") (pin "2") (pinfunction "2_2") (pintype "passive"))
      (node (ref "R80") (pin "1") (pinfunction "1_1") (pintype "passive"))
    )
    (net (code "16") (name "Net-(D1-PadC)") (class "Default")
      (node (ref "D1") (pin "C") (pinfunction "C_C") (pintype "passive"))
      (node (ref "D2") (pin "C") (pinfunction "C_C") (pintype "passive"))
      (node (ref "R33") (pin "1") (pinfunction "1_1") (pintype "passive"))
      (node (ref "R35") (pin "2") (pinfunction "2_2") (pintype "passive"))
    )
    (net (code "17") (name "Net-(D3-PadC)") (class "Default")
      (node (ref "D3") (pin "C") (pinfunction "C_C") (pintype "passive"))
      (node (ref "R84") (pin "2") (pinfunction "2_2") (pintype "passive"))
    )
    (net (code "18") (name "Net-(IC1A-+IN)") (class "Default")
      (node (ref "IC1") (pin "3") (pinfunction "+IN_3") (pintype "input"))
      (node (ref "R10") (pin "1") (pinfunction "1_1") (pintype "passive"))
    )
    (net (code "19") (name "Net-(IC1A--IN)") (class "Default")
      (node (ref "IC1") (pin "1") (pinfunction "OUT_1") (pintype "output"))
      (node (ref "IC1") (pin "2") (pinfunction "-IN_2") (pintype "input"))
      (node (ref "R11") (pin "2") (pinfunction "2_2") (pintype "passive"))
    )
    (net (code "20") (name "Net-(IC1B--IN)") (class "Default")
      (node (ref "IC1") (pin "6") (pinfunction "-IN_6") (pintype "input"))
      (node (ref "R1") (pin "1") (pinfunction "1_1") (pintype "passive"))
      (node (ref "R11") (pin "1") (pinfunction "1_1") (pintype "passive"))
      (node (ref "R12") (pin "2") (pinfunction "S_2") (pintype "passive"))
      (node (ref "R12") (pin "3") (pinfunction "E_3") (pintype "passive"))
      (node (ref "R2") (pin "1") (pinfunction "1_1") (pintype "passive"))
      (node (ref "R7") (pin "2") (pinfunction "2_2") (pintype "passive"))
    )
    (net (code "21") (name "Net-(IC1B-OUT)") (class "Default")
      (node (ref "IC1") (pin "7") (pinfunction "OUT_7") (pintype "output"))
      (node (ref "IC3") (pin "12") (pinfunction "+IN_12") (pintype "input"))
      (node (ref "R3") (pin "2") (pinfunction "2_2") (pintype "passive"))
      (node (ref "R7") (pin "1") (pinfunction "1_1") (pintype "passive"))
    )
    (net (code "22") (name "Net-(IC1C--IN)") (class "Default")
      (node (ref "IC1") (pin "9") (pinfunction "-IN_9") (pintype "input"))
      (node (ref "R3") (pin "1") (pinfunction "1_1") (pintype "passive"))
      (node (ref "R8") (pin "1") (pinfunction "1_1") (pintype "passive"))
      (node (ref "R9") (pin "2") (pinfunction "2_2") (pintype "passive"))
    )
    (net (code "23") (name "Net-(IC1C-OUT)") (class "Default")
      (node (ref "IC1") (pin "8") (pinfunction "OUT_8") (pintype "output"))
      (node (ref "IC3") (pin "10") (pinfunction "+IN_10") (pintype "input"))
      (node (ref "R9") (pin "1") (pinfunction "1_1") (pintype "passive"))
    )
    (net (code "24") (name "Net-(IC1D--IN)") (class "Default")
      (node (ref "IC1") (pin "13") (pinfunction "-IN_13") (pintype "input"))
      (node (ref "R36") (pin "1") (pinfunction "1_1") (pintype "passive"))
      (node (ref "R40") (pin "2") (pinfunction "2_2") (pintype "passive"))
    )
    (net (code "25") (name "Net-(IC1D-OUT)") (class "Default")
      (node (ref "C7") (pin "-") (pinfunction "-_-") (pintype "passive"))
      (node (ref "IC1") (pin "14") (pinfunction "OUT_14") (pintype "output"))
      (node (ref "R40") (pin "1") (pinfunction "1_1") (pintype "passive"))
    )
    (net (code "26") (name "Net-(IC2A--IN)") (class "Default")
      (node (ref "IC2") (pin "2") (pinfunction "-IN_2") (pintype "input"))
      (node (ref "R14") (pin "2") (pinfunction "2_2") (pintype "passive"))
      (node (ref "R5") (pin "1") (pinfunction "1_1") (pintype "passive"))
    )
    (net (code "27") (name "Net-(IC2B-+IN)") (class "Default")
      (node (ref "C1") (pin "+") (pinfunction "+_+") (pintype "passive"))
      (node (ref "IC2") (pin "5") (pinfunction "+IN_5") (pintype "input"))
      (node (ref "R4") (pin "1") (pinfunction "1_1") (pintype "passive"))
      (node (ref "Z1") (pin "C") (pinfunction "C_C") (pintype "passive"))
    )
    (net (code "28") (name "Net-(IC3A-+IN)") (class "Default")
      (node (ref "IC3") (pin "3") (pinfunction "+IN_3") (pintype "input"))
      (node (ref "R16") (pin "1") (pinfunction "1_1") (pintype "passive"))
      (node (ref "R17") (pin "2") (pinfunction "2_2") (pintype "passive"))
    )
    (net (code "29") (name "Net-(IC3A--IN)") (class "Default")
      (node (ref "IC3") (pin "2") (pinfunction "-IN_2") (pintype "input"))
      (node (ref "R26") (pin "1") (pinfunction "1_1") (pintype "passive"))
      (node (ref "R29") (pin "2") (pinfunction "2_2") (pintype "passive"))
    )
    (net (code "30") (name "Net-(IC3B--IN)") (class "Default")
      (node (ref "IC3") (pin "6") (pinfunction "-IN_6") (pintype "input"))
      (node (ref "R19") (pin "1") (pinfunction "1_1") (pintype "passive"))
      (node (ref "R22") (pin "2") (pinfunction "2_2") (pintype "passive"))
    )
    (net (code "31") (name "Net-(IC3B-OUT)") (class "Default")
      (node (ref "IC3") (pin "7") (pinfunction "OUT_7") (pintype "output"))
      (node (ref "R20") (pin "2") (pinfunction "2_2") (pintype "passive"))
      (node (ref "R21") (pin "2") (pinfunction "2_2") (pintype "passive"))
      (node (ref "R22") (pin "1") (pinfunction "1_1") (pintype "passive"))
    )
    (net (code "32") (name "Net-(IC3C--IN)") (class "Default")
      (node (ref "IC3") (pin "9") (pinfunction "-IN_9") (pintype "input"))
      (node (ref "R21") (pin "1") (pinfunction "1_1") (pintype "passive"))
      (node (ref "R24") (pin "2") (pinfunction "2_2") (pintype "passive"))
    )
    (net (code "33") (name "Net-(IC3C-OUT)") (class "Default")
      (node (ref "IC3") (pin "8") (pinfunction "OUT_8") (pintype "output"))
      (node (ref "IC5") (pin "8") (pinfunction "A_8") (pintype "tri_state"))
      (node (ref "R24") (pin "1") (pinfunction "1_1") (pintype "passive"))
      (node (ref "R32") (pin "2") (pinfunction "2_2") (pintype "passive"))
    )
    (net (code "34") (name "Net-(IC3D--IN)") (class "Default")
      (node (ref "IC3") (pin "13") (pinfunction "-IN_13") (pintype "input"))
      (node (ref "R20") (pin "1") (pinfunction "1_1") (pintype "passive"))
      (node (ref "R23") (pin "2") (pinfunction "2_2") (pintype "passive"))
    )
    (net (code "35") (name "Net-(IC3D-OUT)") (class "Default")
      (node (ref "IC3") (pin "14") (pinfunction "OUT_14") (pintype "output"))
      (node (ref "IC5") (pin "3") (pinfunction "B_3") (pintype "tri_state"))
      (node (ref "R23") (pin "1") (pinfunction "1_1") (pintype "passive"))
      (node (ref "R37") (pin "2") (pinfunction "2_2") (pintype "passive"))
      (node (ref "R43") (pin "1") (pinfunction "1_1") (pintype "passive"))
    )
    (net (code "36") (name "Net-(IC4A-+IN)") (class "Default")
      (node (ref "IC4") (pin "5") (pinfunction "+IN_5") (pintype "input"))
      (node (ref "R39") (pin "1") (pinfunction "1_1") (pintype "passive"))
      (node (ref "R42") (pin "2") (pinfunction "2_2") (pintype "passive"))
    )
    (net (code "37") (name "Net-(IC4A--IN)") (class "Default")
      (node (ref "IC4") (pin "4") (pinfunction "-IN_4") (pintype "input"))
      (node (ref "R43") (pin "2") (pinfunction "2_2") (pintype "passive"))
    )
    (net (code "38") (name "Net-(IC4B-+IN)") (class "Default")
      (node (ref "IC4") (pin "7") (pinfunction "+IN_7") (pintype "input"))
      (node (ref "R28") (pin "2") (pinfunction "2_2") (pintype "passive"))
      (node (ref "R32") (pin "1") (pinfunction "1_1") (pintype "passive"))
    )
    (net (code "39") (name "Net-(IC4B--IN)") (class "Default")
      (node (ref "IC4") (pin "6") (pinfunction "-IN_6") (pintype "input"))
      (node (ref "R38") (pin "1") (pinfunction "1_1") (pintype "passive"))
    )
    (net (code "40") (name "Net-(IC4B-OUT)") (class "Default")
      (node (ref "D1") (pin "A") (pinfunction "A_A") (pintype "passive"))
      (node (ref "IC4") (pin "1") (pinfunction "OUT_1") (pintype "open_collector"))
      (node (ref "IC5") (pin "6") (pinfunction "C_6") (pintype "input"))
      (node (ref "R28") (pin "1") (pinfunction "1_1") (pintype "passive"))
      (node (ref "R34") (pin "1") (pinfunction "1_1") (pintype "passive"))
      (node (ref "X21") (pin "1") (pinfunction "P_1") (pintype "passive"))
    )
    (net (code "41") (name "Net-(IC4C-+IN)") (class "Default")
      (node (ref "IC4") (pin "9") (pinfunction "+IN_9") (pintype "input"))
      (node (ref "R27") (pin "2") (pinfunction "2_2") (pintype "passive"))
      (node (ref "R30") (pin "1") (pinfunction "1_1") (pintype "passive"))
    )
    (net (code "42") (name "Net-(IC4C--IN)") (class "Default")
      (node (ref "IC4") (pin "8") (pinfunction "-IN_8") (pintype "input"))
      (node (ref "R37") (pin "1") (pinfunction "1_1") (pintype "passive"))
    )
    (net (code "43") (name "Net-(IC4C-OUT)") (class "Default")
      (node (ref "D2") (pin "A") (pinfunction "A_A") (pintype "passive"))
      (node (ref "IC4") (pin "14") (pinfunction "OUT_14") (pintype "open_collector"))
      (node (ref "IC5") (pin "5") (pinfunction "C_5") (pintype "input"))
      (node (ref "R27") (pin "1") (pinfunction "1_1") (pintype "passive"))
      (node (ref "R31") (pin "1") (pinfunction "1_1") (pintype "passive"))
    )
    (net (code "44") (name "Net-(IC5A-B)") (class "Default")
      (node (ref "IC5") (pin "2") (pinfunction "B_2") (pintype "tri_state"))
      (node (ref "R45") (pin "2") (pinfunction "2_2") (pintype "passive"))
    )
    (net (code "45") (name "Net-(IC5A-C)") (class "Default")
      (node (ref "IC5") (pin "13") (pinfunction "C_13") (pintype "input"))
      (node (ref "Q1") (pin "C") (pinfunction "C_C") (pintype "passive"))
      (node (ref "R25") (pin "1") (pinfunction "1_1") (pintype "passive"))
    )
    (net (code "46") (name "Net-(IC5B-A)") (class "Default")
      (node (ref "IC5") (pin "4") (pinfunction "A_4") (pintype "tri_state"))
      (node (ref "R46") (pin "2") (pinfunction "2_2") (pintype "passive"))
    )
    (net (code "47") (name "Net-(IC5C-B)") (class "Default")
      (node (ref "IC5") (pin "9") (pinfunction "B_9") (pintype "tri_state"))
      (node (ref "R44") (pin "2") (pinfunction "2_2") (pintype "passive"))
    )
    (net (code "48") (name "Net-(IC6A--IN)") (class "Default")
      (node (ref "IC6") (pin "1") (pinfunction "OUT_1") (pintype "output"))
      (node (ref "IC6") (pin "2") (pinfunction "-IN_2") (pintype "input"))
      (node (ref "X8") (pin "1") (pinfunction "P_1") (pintype "passive"))
    )
    (net (code "49") (name "Net-(IC6B--IN)") (class "Default")
      (node (ref "IC6") (pin "6") (pinfunction "-IN_6") (pintype "input"))
      (node (ref "R53") (pin "2") (pinfunction "2_2") (pintype "passive"))
      (node (ref "R57") (pin "2") (pinfunction "2_2") (pintype "passive"))
      (node (ref "R65") (pin "2") (pinfunction "2_2") (pintype "passive"))
      (node (ref "R72") (pin "2") (pinfunction "2_2") (pintype "passive"))
      (node (ref "R80") (pin "2") (pinfunction "2_2") (pintype "passive"))
      (node (ref "R83") (pin "2") (pinfunction "2_2") (pintype "passive"))
    )
    (net (code "50") (name "Net-(IC6B-OUT)") (class "Default")
      (node (ref "C22") (pin "+") (pinfunction "+_+") (pintype "passive"))
      (node (ref "IC6") (pin "7") (pinfunction "OUT_7") (pintype "output"))
      (node (ref "R83") (pin "1") (pinfunction "1_1") (pintype "passive"))
    )
    (net (code "51") (name "Net-(IC7A-CLK)") (class "Default")
      (node (ref "IC7") (pin "3") (pinfunction "CLK_3") (pintype "input"))
      (node (ref "IC8") (pin "14") (pinfunction "OUT_14") (pintype "open_collector"))
      (node (ref "R69") (pin "1") (pinfunction "1_1") (pintype "passive"))
      (node (ref "R70") (pin "2") (pinfunction "2_2") (pintype "passive"))
      (node (ref "R73") (pin "2") (pinfunction "2_2") (pintype "passive"))
    )
    (net (code "52") (name "Net-(IC7A-D)") (class "Default")
      (node (ref "IC7") (pin "2") (pinfunction "~{Q}_2") (pintype "output"))
      (node (ref "IC7") (pin "5") (pinfunction "D_5") (pintype "input"))
    )
    (net (code "53") (name "Net-(IC7A-Q)") (class "Default")
      (node (ref "IC7") (pin "1") (pinfunction "Q_1") (pintype "output"))
      (node (ref "IC7") (pin "11") (pinfunction "CLK_11") (pintype "input"))
      (node (ref "X18") (pin "1") (pinfunction "P_1") (pintype "passive"))
    )
    (net (code "54") (name "Net-(IC7B-D)") (class "Default")
      (node (ref "IC7") (pin "12") (pinfunction "~{Q}_12") (pintype "output"))
      (node (ref "IC7") (pin "9") (pinfunction "D_9") (pintype "input"))
    )
    (net (code "55") (name "Net-(IC7B-Q)") (class "Default")
      (node (ref "IC7") (pin "13") (pinfunction "Q_13") (pintype "output"))
      (node (ref "X19") (pin "1") (pinfunction "P_1") (pintype "passive"))
    )
    (net (code "56") (name "Net-(IC8A-+IN)") (class "Default")
      (node (ref "IC8") (pin "5") (pinfunction "+IN_5") (pintype "input"))
      (node (ref "R47") (pin "2") (pinfunction "2_2") (pintype "passive"))
      (node (ref "R51") (pin "2") (pinfunction "2_2") (pintype "passive"))
    )
    (net (code "57") (name "Net-(IC8A--IN)") (class "Default")
      (node (ref "IC8") (pin "4") (pinfunction "-IN_4") (pintype "input"))
      (node (ref "R50") (pin "2") (pinfunction "2_2") (pintype "passive"))
      (node (ref "R54") (pin "2") (pinfunction "2_2") (pintype "passive"))
      (node (ref "R55") (pin "2") (pinfunction "2_2") (pintype "passive"))
    )
    (net (code "58") (name "Net-(IC8A-OUT)") (class "Default")
      (node (ref "IC8") (pin "2") (pinfunction "OUT_2") (pintype "open_collector"))
      (node (ref "R47") (pin "1") (pinfunction "1_1") (pintype "passive"))
      (node (ref "R48") (pin "2") (pinfunction "2_2") (pintype "passive"))
      (node (ref "R52") (pin "1") (pinfunction "1_1") (pintype "passive"))
    )
    (net (code "59") (name "Net-(IC8B-+IN)") (class "Default")
      (node (ref "IC8") (pin "7") (pinfunction "+IN_7") (pintype "input"))
      (node (ref "R59") (pin "2") (pinfunction "2_2") (pintype "passive"))
      (node (ref "R60") (pin "1") (pinfunction "1_1") (pintype "passive"))
    )
    (net (code "60") (name "Net-(IC8B--IN)") (class "Default")
      (node (ref "IC8") (pin "6") (pinfunction "-IN_6") (pintype "input"))
      (node (ref "R55") (pin "1") (pinfunction "1_1") (pintype "passive"))
      (node (ref "R67") (pin "2") (pinfunction "2_2") (pintype "passive"))
    )
    (net (code "61") (name "Net-(IC8B-OUT)") (class "Default")
      (node (ref "IC8") (pin "1") (pinfunction "OUT_1") (pintype "open_collector"))
      (node (ref "R60") (pin "2") (pinfunction "2_2") (pintype "passive"))
      (node (ref "R61") (pin "1") (pinfunction "1_1") (pintype "passive"))
      (node (ref "R64") (pin "1") (pinfunction "1_1") (pintype "passive"))
    )
    (net (code "62") (name "Net-(IC8C-+IN)") (class "Default")
      (node (ref "IC8") (pin "9") (pinfunction "+IN_9") (pintype "input"))
      (node (ref "R68") (pin "1") (pinfunction "1_1") (pintype "passive"))
      (node (ref "R69") (pin "2") (pinfunction "2_2") (pintype "passive"))
    )
    (net (code "63") (name "Net-(IC8C--IN)") (class "Default")
      (node (ref "IC8") (pin "8") (pinfunction "-IN_8") (pintype "input"))
      (node (ref "R67") (pin "1") (pinfunction "1_1") (pintype "passive"))
      (node (ref "R76") (pin "1") (pinfunction "1_1") (pintype "passive"))
    )
    (net (code "64") (name "Net-(IC8D-+IN)") (class "Default")
      (node (ref "IC8") (pin "11") (pinfunction "+IN_11") (pintype "input"))
      (node (ref "R77") (pin "2") (pinfunction "2_2") (pintype "passive"))
      (node (ref "R78") (pin "1") (pinfunction "1_1") (pintype "passive"))
    )
    (net (code "65") (name "Net-(IC8D--IN)") (class "Default")
      (node (ref "IC8") (pin "10") (pinfunction "-IN_10") (pintype "input"))
      (node (ref "R76") (pin "2") (pinfunction "2_2") (pintype "passive"))
      (node (ref "R81") (pin "2") (pinfunction "2_2") (pintype "passive"))
    )
    (net (code "66") (name "Net-(IC8D-OUT)") (class "Default")
      (node (ref "IC8") (pin "13") (pinfunction "OUT_13") (pintype "open_collector"))
      (node (ref "R78") (pin "2") (pinfunction "2_2") (pintype "passive"))
      (node (ref "R79") (pin "1") (pinfunction "1_1") (pintype "passive"))
      (node (ref "R82") (pin "2") (pinfunction "2_2") (pintype "passive"))
    )
    (net (code "67") (name "Net-(IC9A-+IN)") (class "Default")
      (node (ref "IC9") (pin "3") (pinfunction "+IN_3") (pintype "input"))
      (node (ref "R52") (pin "2") (pinfunction "2_2") (pintype "passive"))
      (node (ref "R64") (pin "2") (pinfunction "2_2") (pintype "passive"))
      (node (ref "R73") (pin "1") (pinfunction "1_1") (pintype "passive"))
      (node (ref "R74") (pin "2") (pinfunction "2_2") (pintype "passive"))
      (node (ref "R82") (pin "1") (pinfunction "1_1") (pintype "passive"))
    )
    (net (code "68") (name "Net-(IC9A--IN)") (class "Default")
      (node (ref "IC9") (pin "1") (pinfunction "OUT_1") (pintype "output"))
      (node (ref "IC9") (pin "2") (pinfunction "-IN_2") (pintype "input"))
      (node (ref "X16") (pin "1") (pinfunction "P_1") (pintype "passive"))
    )
    (net (code "69") (name "Net-(IC9B--IN)") (class "Default")
      (node (ref "IC9") (pin "6") (pinfunction "-IN_6") (pintype "input"))
      (node (ref "R58") (pin "1") (pinfunction "1_1") (pintype "passive"))
      (node (ref "R63") (pin "2") (pinfunction "2_2") (pintype "passive"))
      (node (ref "R66") (pin "2") (pinfunction "2_2") (pintype "passive"))
    )
    (net (code "70") (name "Net-(IC9B-OUT)") (class "Default")
      (node (ref "IC9") (pin "7") (pinfunction "OUT_7") (pintype "output"))
      (node (ref "R54") (pin "1") (pinfunction "1_1") (pintype "passive"))
      (node (ref "R58") (pin "2") (pinfunction "2_2") (pintype "passive"))
    )
    (net (code "71") (name "Net-(Q1-PadB)") (class "Default")
      (node (ref "Q1") (pin "B") (pinfunction "B_B") (pintype "passive"))
      (node (ref "R33") (pin "2") (pinfunction "2_2") (pintype "passive"))
    )
    (net (code "72") (name "Net-(Q2-D)") (class "Default")
      (node (ref "C23") (pin "1") (pinfunction "1_1") (pintype "passive"))
      (node (ref "Q2") (pin "3") (pinfunction "D_3") (pintype "passive"))
      (node (ref "R85") (pin "2") (pinfunction "2_2") (pintype "passive"))
    )
    (net (code "73") (name "Net-(Q2-G)") (class "Default")
      (node (ref "Q2") (pin "1") (pinfunction "G_1") (pintype "passive"))
      (node (ref "R84") (pin "1") (pinfunction "1_1") (pintype "passive"))
      (node (ref "R86") (pin "1") (pinfunction "1_1") (pintype "passive"))
    )
    (net (code "74") (name "Net-(Q3-D)") (class "Default")
      (node (ref "Q3") (pin "3") (pinfunction "D_3") (pintype "passive"))
      (node (ref "R88") (pin "1") (pinfunction "1_1") (pintype "passive"))
    )
    (net (code "75") (name "Net-(Q3-G)") (class "Default")
      (node (ref "Q3") (pin "1") (pinfunction "G_1") (pintype "passive"))
      (node (ref "R85") (pin "1") (pinfunction "1_1") (pintype "passive"))
      (node (ref "R87") (pin "1") (pinfunction "1_1") (pintype "passive"))
    )
    (net (code "76") (name "Net-(R13-E)") (class "Default")
      (node (ref "R13") (pin "2") (pinfunction "S_2") (pintype "passive"))
      (node (ref "R13") (pin "3") (pinfunction "E_3") (pintype "passive"))
      (node (ref "R8") (pin "2") (pinfunction "2_2") (pintype "passive"))
    )
    (net (code "77") (name "Net-(X1-P)") (class "Default")
      (node (ref "R1") (pin "2") (pinfunction "2_2") (pintype "passive"))
      (node (ref "X1") (pin "1") (pinfunction "P_1") (pintype "passive"))
    )
    (net (code "78") (name "Net-(X2-P)") (class "Default")
      (node (ref "R2") (pin "2") (pinfunction "2_2") (pintype "passive"))
      (node (ref "X2") (pin "1") (pinfunction "P_1") (pintype "passive"))
    )
    (net (code "79") (name "Net-(X3-P)") (class "Default")
      (node (ref "C2") (pin "1") (pinfunction "1_1") (pintype "passive"))
      (node (ref "R10") (pin "2") (pinfunction "2_2") (pintype "passive"))
      (node (ref "X3") (pin "1") (pinfunction "P_1") (pintype "passive"))
    )
    (net (code "80") (name "Net-(X4-P)") (class "Default")
      (node (ref "C3") (pin "+") (pinfunction "+_+") (pintype "passive"))
      (node (ref "R6") (pin "1") (pinfunction "1_1") (pintype "passive"))
      (node (ref "X4") (pin "1") (pinfunction "P_1") (pintype "passive"))
      (node (ref "Z2") (pin "C") (pinfunction "C_C") (pintype "passive"))
    )
    (net (code "81") (name "Net-(X5-P)") (class "Default")
      (node (ref "C6") (pin "-") (pinfunction "-_-") (pintype "passive"))
      (node (ref "R18") (pin "1") (pinfunction "1_1") (pintype "passive"))
      (node (ref "X5") (pin "1") (pinfunction "P_1") (pintype "passive"))
      (node (ref "Z3") (pin "A") (pinfunction "A_A") (pintype "passive"))
    )
    (net (code "82") (name "Net-(X6-P)") (class "Default")
      (node (ref "C8") (pin "+") (pinfunction "+_+") (pintype "passive"))
      (node (ref "X6") (pin "1") (pinfunction "P_1") (pintype "passive"))
    )
    (net (code "83") (name "Net-(X9-P)") (class "Default")
      (node (ref "C17") (pin "1") (pinfunction "1_1") (pintype "passive"))
      (node (ref "X9") (pin "1") (pinfunction "P_1") (pintype "passive"))
    )
    (net (code "84") (name "Net-(X10-P)") (class "Default")
      (node (ref "C18") (pin "1") (pinfunction "1_1") (pintype "passive"))
      (node (ref "X10") (pin "1") (pinfunction "P_1") (pintype "passive"))
    )
    (net (code "85") (name "Net-(X11-P)") (class "Default")
      (node (ref "C19") (pin "1") (pinfunction "1_1") (pintype "passive"))
      (node (ref "X11") (pin "1") (pinfunction "P_1") (pintype "passive"))
    )
    (net (code "86") (name "Net-(X12-P)") (class "Default")
      (node (ref "R63") (pin "1") (pinfunction "1_1") (pintype "passive"))
      (node (ref "X12") (pin "1") (pinfunction "P_1") (pintype "passive"))
    )
    (net (code "87") (name "Net-(X13-P)") (class "Default")
      (node (ref "C20") (pin "1") (pinfunction "1_1") (pintype "passive"))
      (node (ref "X13") (pin "1") (pinfunction "P_1") (pintype "passive"))
    )
    (net (code "88") (name "Net-(X14-P)") (class "Default")
      (node (ref "R66") (pin "1") (pinfunction "1_1") (pintype "passive"))
      (node (ref "X14") (pin "1") (pinfunction "P_1") (pintype "passive"))
    )
    (net (code "89") (name "Net-(X15-P)") (class "Default")
      (node (ref "C21") (pin "1") (pinfunction "1_1") (pintype "passive"))
      (node (ref "X15") (pin "1") (pinfunction "P_1") (pintype "passive"))
    )
    (net (code "90") (name "Net-(X17-P)") (class "Default")
      (node (ref "C22") (pin "-") (pinfunction "-_-") (pintype "passive"))
      (node (ref "X17") (pin "1") (pinfunction "P_1") (pintype "passive"))
    )
    (net (code "91") (name "Net-(X20-P)") (class "Default")
      (node (ref "LED1") (pin "A") (pinfunction "A_A") (pintype "passive"))
      (node (ref "R88") (pin "2") (pinfunction "2_2") (pintype "passive"))
      (node (ref "X20") (pin "1") (pinfunction "P_1") (pintype "passive"))
    )
  )
)
